# Power.net
KiCad netlist of a schematic drawn in Altium Designer
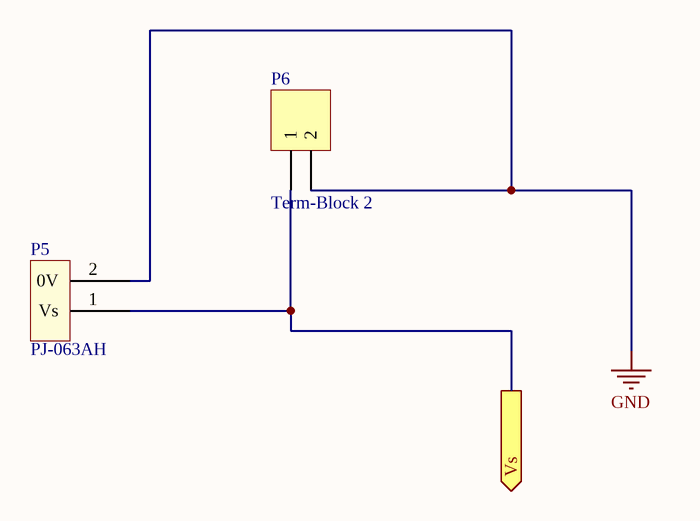
[diagram p0: Power.SchDoc]

(export (version "E")
  (design (tool "Eeschema 10.0.6"))
  (components
    (comp (ref "P5")
      (value "PJ-063AH")
      (footprint "PJ-063AH")
      (libsource (lib "Elec391_Components") (part "PJ-063AH"))
    )
    (comp (ref "P6")
      (value "Term-Block 2")
      (footprint "TERM-BLOCK-5.08MM-2POS")
      (description "Terminal-Block 1x2")
      (fields (field (name "PUBLISHER") "Altium Limited"))
      (libsource (lib "PartsDatabaseV16.1") (part "C-Block2"))
    )
  )
  (nets
    (net (code "1") (name "/Vs") (class "Default")
      (node (ref "P5") (pin "1") (pinfunction "Vs_1") (pintype "passive"))
      (node (ref "P6") (pin "1") (pinfunction "1_1") (pintype "passive"))
    )
    (net (code "2") (name "GND") (class "Default")
      (node (ref "P5") (pin "2") (pinfunction "0V_2") (pintype "passive"))
      (node (ref "P6") (pin "2") (pinfunction "2_2") (pintype "passive"))
    )
  )
)
